# CFO_europroto_atmega328_mcp4822.net
KiCad netlist of a schematic drawn in EAGLE
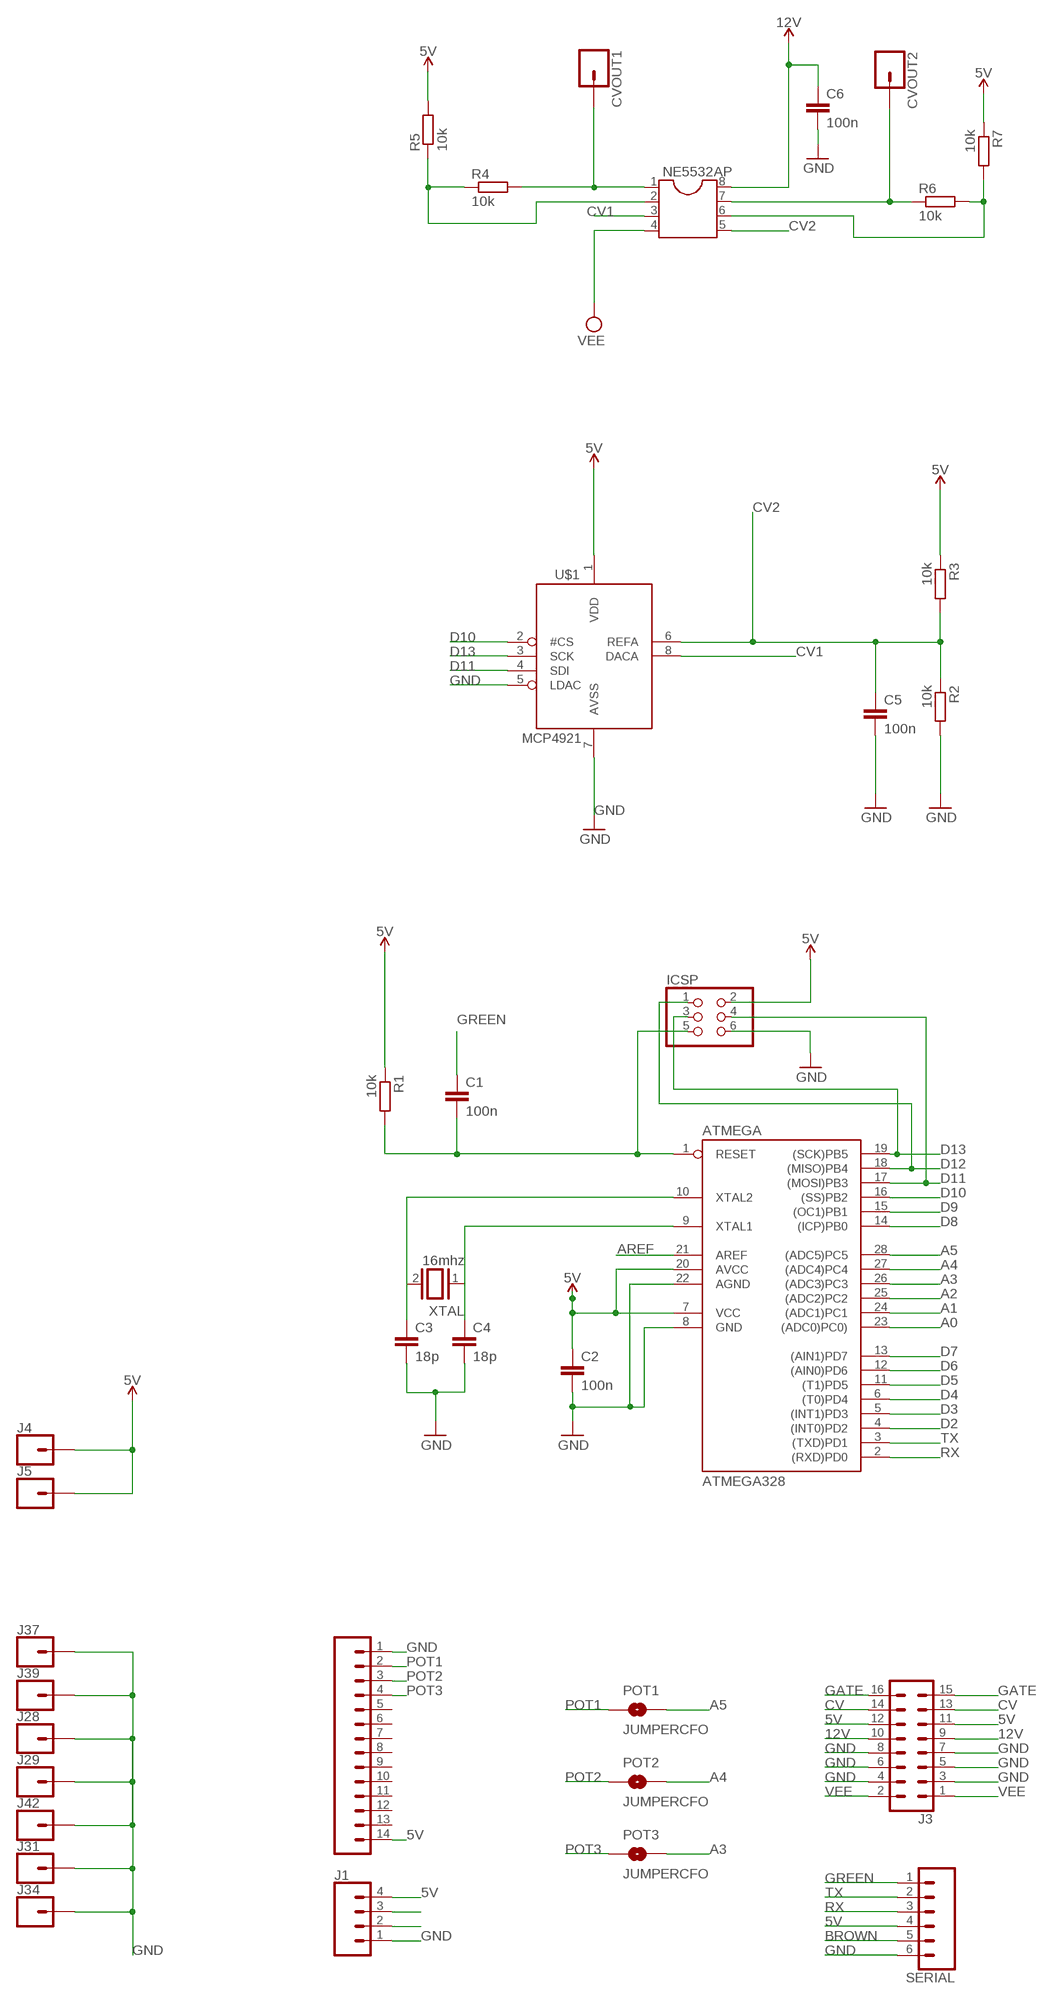
[diagram p0: schematic, sheet 1]

(export (version "E")
  (design (tool "Eeschema 10.0.6"))
  (components
    (comp (ref "ATMEGA")
      (value "ATMEGA328")
      (footprint "eagle-import:DIL28-3")
      (libsource (lib "eagle-import") (part "AT90S4433P"))
    )
    (comp (ref "C1")
      (value "100n")
      (footprint "eagle-import:C050-025X075")
      (libsource (lib "eagle-import") (part "C-EU050-025X075"))
    )
    (comp (ref "C2")
      (value "100n")
      (footprint "eagle-import:C050-025X075")
      (libsource (lib "eagle-import") (part "C-EU050-025X075"))
    )
    (comp (ref "C3")
      (value "18p")
      (footprint "eagle-import:C050-025X075")
      (libsource (lib "eagle-import") (part "C-EU050-025X075"))
    )
    (comp (ref "C4")
      (value "18p")
      (footprint "eagle-import:C050-025X075")
      (libsource (lib "eagle-import") (part "C-EU050-025X075"))
    )
    (comp (ref "C5")
      (value "100n")
      (footprint "eagle-import:C050-025X075")
      (libsource (lib "eagle-import") (part "C-EU050-025X075"))
    )
    (comp (ref "C6")
      (value "100n")
      (footprint "eagle-import:C050-025X075")
      (libsource (lib "eagle-import") (part "C-EU050-025X075"))
    )
    (comp (ref "CVOUT1")
      (value "CONN_01")
      (footprint "eagle-import:1X01")
      (libsource (lib "eagle-import") (part "CONN_01"))
    )
    (comp (ref "CVOUT2")
      (value "CONN_01")
      (footprint "eagle-import:1X01")
      (libsource (lib "eagle-import") (part "CONN_01"))
    )
    (comp (ref "ICSP")
      (value "PINHD-2X3")
      (footprint "eagle-import:2X03")
      (libsource (lib "eagle-import") (part "PINHD-2X3"))
    )
    (comp (ref "J1")
      (value "CONN_04")
      (footprint "eagle-import:1X04")
      (fields (field (name "SPICEPREFIX") "E"))
      (libsource (lib "eagle-import") (part "CONN_04"))
    )
    (comp (ref "J2")
      (value "CONN_14SQUARE")
      (footprint "eagle-import:1X14")
      (fields (field (name "SPICEPREFIX") "X"))
      (libsource (lib "eagle-import") (part "CONN_14SQUARE"))
    )
    (comp (ref "J3")
      (value "CONN_08X2_SHROUD")
      (footprint "eagle-import:2X8-SHROUDED_LOCK")
      (libsource (lib "eagle-import") (part "CONN_08X2_SHROUD"))
    )
    (comp (ref "J4")
      (value "CONN_01")
      (footprint "eagle-import:1X01")
      (libsource (lib "eagle-import") (part "CONN_01"))
    )
    (comp (ref "J5")
      (value "CONN_01")
      (footprint "eagle-import:1X01")
      (libsource (lib "eagle-import") (part "CONN_01"))
    )
    (comp (ref "J28")
      (value "CONN_01")
      (footprint "eagle-import:1X01")
      (libsource (lib "eagle-import") (part "CONN_01"))
    )
    (comp (ref "J29")
      (value "CONN_01")
      (footprint "eagle-import:1X01")
      (libsource (lib "eagle-import") (part "CONN_01"))
    )
    (comp (ref "J31")
      (value "CONN_01")
      (footprint "eagle-import:1X01")
      (libsource (lib "eagle-import") (part "CONN_01"))
    )
    (comp (ref "J34")
      (value "CONN_01")
      (footprint "eagle-import:1X01")
      (libsource (lib "eagle-import") (part "CONN_01"))
    )
    (comp (ref "J37")
      (value "CONN_01")
      (footprint "eagle-import:1X01")
      (libsource (lib "eagle-import") (part "CONN_01"))
    )
    (comp (ref "J39")
      (value "CONN_01")
      (footprint "eagle-import:1X01")
      (libsource (lib "eagle-import") (part "CONN_01"))
    )
    (comp (ref "J42")
      (value "CONN_01")
      (footprint "eagle-import:1X01")
      (libsource (lib "eagle-import") (part "CONN_01"))
    )
    (comp (ref "NE5532AP")
      (value "DIL8")
      (footprint "eagle-import:DIL08")
      (libsource (lib "eagle-import") (part "DIL8"))
    )
    (comp (ref "POT1")
      (value "JUMPERCFO")
      (footprint "eagle-import:SMT-JUMPER_2_NO_NO-SILK_ROUND")
      (libsource (lib "eagle-import") (part "JUMPERCFO"))
    )
    (comp (ref "POT2")
      (value "JUMPERCFO")
      (footprint "eagle-import:SMT-JUMPER_2_NO_NO-SILK_ROUND")
      (libsource (lib "eagle-import") (part "JUMPERCFO"))
    )
    (comp (ref "POT3")
      (value "JUMPERCFO")
      (footprint "eagle-import:SMT-JUMPER_2_NO_NO-SILK_ROUND")
      (libsource (lib "eagle-import") (part "JUMPERCFO"))
    )
    (comp (ref "R1")
      (value "10k")
      (footprint "eagle-import:0207_10")
      (libsource (lib "eagle-import") (part "R-EU_0207/10"))
    )
    (comp (ref "R2")
      (value "10k")
      (footprint "eagle-import:0207_10")
      (libsource (lib "eagle-import") (part "R-EU_0207/10"))
    )
    (comp (ref "R3")
      (value "10k")
      (footprint "eagle-import:0207_10")
      (libsource (lib "eagle-import") (part "R-EU_0207/10"))
    )
    (comp (ref "R4")
      (value "10k")
      (footprint "eagle-import:0207_10")
      (libsource (lib "eagle-import") (part "R-EU_0207/10"))
    )
    (comp (ref "R5")
      (value "10k")
      (footprint "eagle-import:0207_10")
      (libsource (lib "eagle-import") (part "R-EU_0207/10"))
    )
    (comp (ref "R6")
      (value "10k")
      (footprint "eagle-import:0207_10")
      (libsource (lib "eagle-import") (part "R-EU_0207/10"))
    )
    (comp (ref "R7")
      (value "10k")
      (footprint "eagle-import:0207_10")
      (libsource (lib "eagle-import") (part "R-EU_0207/10"))
    )
    (comp (ref "SERIAL")
      (value "CONN_06SILK_FEMALE_PTH")
      (footprint "eagle-import:1X06")
      (libsource (lib "eagle-import") (part "CONN_06SILK_FEMALE_PTH"))
    )
    (comp (ref "U$1")
      (value "MCP4921")
      (footprint "eagle-import:DIL08")
      (libsource (lib "eagle-import") (part "MCP4921"))
    )
    (comp (ref "XTAL")
      (value "16mhz")
      (footprint "eagle-import:QS")
      (libsource (lib "eagle-import") (part "XTAL/S"))
    )
  )
  (nets
    (net (code "1") (name "/A0") (class "Default")
      (node (ref "ATMEGA") (pin "23") (pinfunction "(ADC0)PC0)_23") (pintype "bidirectional"))
    )
    (net (code "2") (name "/A1") (class "Default")
      (node (ref "ATMEGA") (pin "24") (pinfunction "(ADC1)PC1_24") (pintype "bidirectional"))
    )
    (net (code "3") (name "/A2") (class "Default")
      (node (ref "ATMEGA") (pin "25") (pinfunction "(ADC2)PC2_25") (pintype "bidirectional"))
    )
    (net (code "4") (name "/A3") (class "Default")
      (node (ref "ATMEGA") (pin "26") (pinfunction "(ADC3)PC3_26") (pintype "bidirectional"))
      (node (ref "POT3") (pin "2") (pinfunction "2_2") (pintype "passive"))
    )
    (net (code "5") (name "/A4") (class "Default")
      (node (ref "ATMEGA") (pin "27") (pinfunction "(ADC4)PC4_27") (pintype "bidirectional"))
      (node (ref "POT2") (pin "2") (pinfunction "2_2") (pintype "passive"))
    )
    (net (code "6") (name "/A5") (class "Default")
      (node (ref "ATMEGA") (pin "28") (pinfunction "(ADC5)PC5_28") (pintype "bidirectional"))
      (node (ref "POT1") (pin "2") (pinfunction "2_2") (pintype "passive"))
    )
    (net (code "7") (name "/AREF") (class "Default")
      (node (ref "ATMEGA") (pin "21") (pinfunction "AREF_21") (pintype "passive"))
    )
    (net (code "8") (name "/BROWN") (class "Default")
      (node (ref "SERIAL") (pin "5") (pinfunction "5_5") (pintype "passive"))
    )
    (net (code "9") (name "/CV") (class "Default")
      (node (ref "J3") (pin "13") (pinfunction "13_13") (pintype "passive"))
      (node (ref "J3") (pin "14") (pinfunction "14_14") (pintype "passive"))
    )
    (net (code "10") (name "/CV1") (class "Default")
      (node (ref "NE5532AP") (pin "3") (pinfunction "3_3") (pintype "passive"))
      (node (ref "U$1") (pin "8") (pinfunction "DACA_8") (pintype "output"))
    )
    (net (code "11") (name "/CV2") (class "Default")
      (node (ref "C5") (pin "1") (pinfunction "1_1") (pintype "passive"))
      (node (ref "NE5532AP") (pin "5") (pinfunction "5_5") (pintype "passive"))
      (node (ref "R2") (pin "1") (pinfunction "1_1") (pintype "passive"))
      (node (ref "R3") (pin "2") (pinfunction "2_2") (pintype "passive"))
      (node (ref "U$1") (pin "6") (pinfunction "REFA_6") (pintype "input"))
    )
    (net (code "12") (name "/D2") (class "Default")
      (node (ref "ATMEGA") (pin "4") (pinfunction "(INT0)PD2_4") (pintype "bidirectional"))
    )
    (net (code "13") (name "/D3") (class "Default")
      (node (ref "ATMEGA") (pin "5") (pinfunction "(INT1)PD3_5") (pintype "bidirectional"))
    )
    (net (code "14") (name "/D4") (class "Default")
      (node (ref "ATMEGA") (pin "6") (pinfunction "(T0)PD4_6") (pintype "bidirectional"))
    )
    (net (code "15") (name "/D5") (class "Default")
      (node (ref "ATMEGA") (pin "11") (pinfunction "(T1)PD5_11") (pintype "bidirectional"))
    )
    (net (code "16") (name "/D6") (class "Default")
      (node (ref "ATMEGA") (pin "12") (pinfunction "(AIN0)PD6_12") (pintype "bidirectional"))
    )
    (net (code "17") (name "/D7") (class "Default")
      (node (ref "ATMEGA") (pin "13") (pinfunction "(AIN1)PD7_13") (pintype "bidirectional"))
    )
    (net (code "18") (name "/D8") (class "Default")
      (node (ref "ATMEGA") (pin "14") (pinfunction "(ICP)PB0_14") (pintype "bidirectional"))
    )
    (net (code "19") (name "/D9") (class "Default")
      (node (ref "ATMEGA") (pin "15") (pinfunction "(OC1)PB1_15") (pintype "bidirectional"))
    )
    (net (code "20") (name "/D10") (class "Default")
      (node (ref "ATMEGA") (pin "16") (pinfunction "(SS)PB2_16") (pintype "bidirectional"))
      (node (ref "U$1") (pin "2") (pinfunction "#CS_2") (pintype "input"))
    )
    (net (code "21") (name "/D11") (class "Default")
      (node (ref "ATMEGA") (pin "17") (pinfunction "(MOSI)PB3_17") (pintype "bidirectional"))
      (node (ref "ICSP") (pin "4") (pinfunction "4_4") (pintype "passive"))
      (node (ref "U$1") (pin "4") (pinfunction "SDI_4") (pintype "input"))
    )
    (net (code "22") (name "/D12") (class "Default")
      (node (ref "ATMEGA") (pin "18") (pinfunction "(MISO)PB4_18") (pintype "bidirectional"))
      (node (ref "ICSP") (pin "1") (pinfunction "1_1") (pintype "passive"))
    )
    (net (code "23") (name "/D13") (class "Default")
      (node (ref "ATMEGA") (pin "19") (pinfunction "(SCK)PB5_19") (pintype "bidirectional"))
      (node (ref "ICSP") (pin "3") (pinfunction "3_3") (pintype "passive"))
      (node (ref "U$1") (pin "3") (pinfunction "SCK_3") (pintype "input"))
    )
    (net (code "24") (name "/GATE") (class "Default")
      (node (ref "J3") (pin "15") (pinfunction "15_15") (pintype "passive"))
      (node (ref "J3") (pin "16") (pinfunction "16_16") (pintype "passive"))
    )
    (net (code "25") (name "/GREEN") (class "Default")
      (node (ref "C1") (pin "1") (pinfunction "1_1") (pintype "passive"))
      (node (ref "SERIAL") (pin "1") (pinfunction "1_1") (pintype "passive"))
    )
    (net (code "26") (name "/POT1") (class "Default")
      (node (ref "J2") (pin "2") (pinfunction "2_2") (pintype "passive"))
      (node (ref "POT1") (pin "1") (pinfunction "1_1") (pintype "passive"))
    )
    (net (code "27") (name "/POT2") (class "Default")
      (node (ref "J2") (pin "3") (pinfunction "3_3") (pintype "passive"))
      (node (ref "POT2") (pin "1") (pinfunction "1_1") (pintype "passive"))
    )
    (net (code "28") (name "/POT3") (class "Default")
      (node (ref "J2") (pin "4") (pinfunction "4_4") (pintype "passive"))
      (node (ref "POT3") (pin "1") (pinfunction "1_1") (pintype "passive"))
    )
    (net (code "29") (name "/RX") (class "Default")
      (node (ref "ATMEGA") (pin "2") (pinfunction "(RXD)PD0_2") (pintype "bidirectional"))
      (node (ref "SERIAL") (pin "3") (pinfunction "3_3") (pintype "passive"))
    )
    (net (code "30") (name "/TX") (class "Default")
      (node (ref "ATMEGA") (pin "3") (pinfunction "(TXD)PD1_3") (pintype "bidirectional"))
      (node (ref "SERIAL") (pin "2") (pinfunction "2_2") (pintype "passive"))
    )
    (net (code "31") (name "5V") (class "Default")
      (node (ref "ATMEGA") (pin "20") (pinfunction "AVCC_20") (pintype "power_in"))
      (node (ref "ATMEGA") (pin "7") (pinfunction "VCC_7") (pintype "power_in"))
      (node (ref "C2") (pin "1") (pinfunction "1_1") (pintype "passive"))
      (node (ref "ICSP") (pin "2") (pinfunction "2_2") (pintype "passive"))
      (node (ref "J1") (pin "4") (pinfunction "4_4") (pintype "passive"))
      (node (ref "J2") (pin "14") (pinfunction "14_14") (pintype "passive"))
      (node (ref "J3") (pin "11") (pinfunction "11_11") (pintype "passive"))
      (node (ref "J3") (pin "12") (pinfunction "12_12") (pintype "passive"))
      (node (ref "J4") (pin "1") (pinfunction "1_1") (pintype "passive"))
      (node (ref "J5") (pin "1") (pinfunction "1_1") (pintype "passive"))
      (node (ref "R1") (pin "1") (pinfunction "1_1") (pintype "passive"))
      (node (ref "R3") (pin "1") (pinfunction "1_1") (pintype "passive"))
      (node (ref "R5") (pin "2") (pinfunction "2_2") (pintype "passive"))
      (node (ref "R7") (pin "1") (pinfunction "1_1") (pintype "passive"))
      (node (ref "SERIAL") (pin "4") (pinfunction "4_4") (pintype "passive"))
      (node (ref "U$1") (pin "1") (pinfunction "VDD_1") (pintype "power_in"))
    )
    (net (code "32") (name "12V") (class "Default")
      (node (ref "C6") (pin "1") (pinfunction "1_1") (pintype "passive"))
      (node (ref "J3") (pin "10") (pinfunction "10_10") (pintype "passive"))
      (node (ref "J3") (pin "9") (pinfunction "9_9") (pintype "passive"))
      (node (ref "NE5532AP") (pin "8") (pinfunction "8_8") (pintype "passive"))
    )
    (net (code "33") (name "GND") (class "Default")
      (node (ref "ATMEGA") (pin "22") (pinfunction "AGND_22") (pintype "power_in"))
      (node (ref "ATMEGA") (pin "8") (pinfunction "GND_8") (pintype "power_in"))
      (node (ref "C2") (pin "2") (pinfunction "2_2") (pintype "passive"))
      (node (ref "C3") (pin "2") (pinfunction "2_2") (pintype "passive"))
      (node (ref "C4") (pin "2") (pinfunction "2_2") (pintype "passive"))
      (node (ref "C5") (pin "2") (pinfunction "2_2") (pintype "passive"))
      (node (ref "C6") (pin "2") (pinfunction "2_2") (pintype "passive"))
      (node (ref "ICSP") (pin "6") (pinfunction "6_6") (pintype "passive"))
      (node (ref "J1") (pin "1") (pinfunction "1_1") (pintype "passive"))
      (node (ref "J2") (pin "1") (pinfunction "1_1") (pintype "passive"))
      (node (ref "J28") (pin "1") (pinfunction "1_1") (pintype "passive"))
      (node (ref "J29") (pin "1") (pinfunction "1_1") (pintype "passive"))
      (node (ref "J3") (pin "3") (pinfunction "3_3") (pintype "passive"))
      (node (ref "J3") (pin "4") (pinfunction "4_4") (pintype "passive"))
      (node (ref "J3") (pin "5") (pinfunction "5_5") (pintype "passive"))
      (node (ref "J3") (pin "6") (pinfunction "6_6") (pintype "passive"))
      (node (ref "J3") (pin "7") (pinfunction "7_7") (pintype "passive"))
      (node (ref "J3") (pin "8") (pinfunction "8_8") (pintype "passive"))
      (node (ref "J31") (pin "1") (pinfunction "1_1") (pintype "passive"))
      (node (ref "J34") (pin "1") (pinfunction "1_1") (pintype "passive"))
      (node (ref "J37") (pin "1") (pinfunction "1_1") (pintype "passive"))
      (node (ref "J39") (pin "1") (pinfunction "1_1") (pintype "passive"))
      (node (ref "J42") (pin "1") (pinfunction "1_1") (pintype "passive"))
      (node (ref "R2") (pin "2") (pinfunction "2_2") (pintype "passive"))
      (node (ref "SERIAL") (pin "6") (pinfunction "6_6") (pintype "passive"))
      (node (ref "U$1") (pin "5") (pinfunction "LDAC_5") (pintype "input"))
      (node (ref "U$1") (pin "7") (pinfunction "AVSS_7") (pintype "power_in"))
    )
    (net (code "34") (name "Net-(ATMEGA-RESET)") (class "Default")
      (node (ref "ATMEGA") (pin "1") (pinfunction "RESET_1") (pintype "input"))
      (node (ref "C1") (pin "2") (pinfunction "2_2") (pintype "passive"))
      (node (ref "ICSP") (pin "5") (pinfunction "5_5") (pintype "passive"))
      (node (ref "R1") (pin "2") (pinfunction "2_2") (pintype "passive"))
    )
    (net (code "35") (name "Net-(ATMEGA-XTAL1)") (class "Default")
      (node (ref "ATMEGA") (pin "9") (pinfunction "XTAL1_9") (pintype "bidirectional"))
      (node (ref "C4") (pin "1") (pinfunction "1_1") (pintype "passive"))
      (node (ref "XTAL") (pin "1") (pinfunction "1_1") (pintype "passive"))
    )
    (net (code "36") (name "Net-(ATMEGA-XTAL2)") (class "Default")
      (node (ref "ATMEGA") (pin "10") (pinfunction "XTAL2_10") (pintype "bidirectional"))
      (node (ref "C3") (pin "1") (pinfunction "1_1") (pintype "passive"))
      (node (ref "XTAL") (pin "2") (pinfunction "2_2") (pintype "passive"))
    )
    (net (code "37") (name "Net-(CVOUT1-Pad1)") (class "Default")
      (node (ref "CVOUT1") (pin "1") (pinfunction "1_1") (pintype "passive"))
      (node (ref "NE5532AP") (pin "1") (pinfunction "1_1") (pintype "passive"))
      (node (ref "R4") (pin "2") (pinfunction "2_2") (pintype "passive"))
    )
    (net (code "38") (name "Net-(CVOUT2-Pad1)") (class "Default")
      (node (ref "CVOUT2") (pin "1") (pinfunction "1_1") (pintype "passive"))
      (node (ref "NE5532AP") (pin "7") (pinfunction "7_7") (pintype "passive"))
      (node (ref "R6") (pin "1") (pinfunction "1_1") (pintype "passive"))
    )
    (net (code "39") (name "Net-(NE5532AP-Pad2)") (class "Default")
      (node (ref "NE5532AP") (pin "2") (pinfunction "2_2") (pintype "passive"))
      (node (ref "R4") (pin "1") (pinfunction "1_1") (pintype "passive"))
      (node (ref "R5") (pin "1") (pinfunction "1_1") (pintype "passive"))
    )
    (net (code "40") (name "Net-(NE5532AP-Pad6)") (class "Default")
      (node (ref "NE5532AP") (pin "6") (pinfunction "6_6") (pintype "passive"))
      (node (ref "R6") (pin "2") (pinfunction "2_2") (pintype "passive"))
      (node (ref "R7") (pin "2") (pinfunction "2_2") (pintype "passive"))
    )
    (net (code "41") (name "VEE") (class "Default")
      (node (ref "J3") (pin "1") (pinfunction "1_1") (pintype "passive"))
      (node (ref "J3") (pin "2") (pinfunction "2_2") (pintype "passive"))
      (node (ref "NE5532AP") (pin "4") (pinfunction "4_4") (pintype "passive"))
    )
    (net (code "42") (name "unconnected-(J1-Pad2)") (class "Default")
      (node (ref "J1") (pin "2") (pinfunction "2_2") (pintype "passive"))
    )
    (net (code "43") (name "unconnected-(J1-Pad3)") (class "Default")
      (node (ref "J1") (pin "3") (pinfunction "3_3") (pintype "passive"))
    )
    (net (code "44") (name "unconnected-(J2-Pad5)") (class "Default")
      (node (ref "J2") (pin "5") (pinfunction "5_5") (pintype "passive"))
    )
    (net (code "45") (name "unconnected-(J2-Pad6)") (class "Default")
      (node (ref "J2") (pin "6") (pinfunction "6_6") (pintype "passive"))
    )
    (net (code "46") (name "unconnected-(J2-Pad7)") (class "Default")
      (node (ref "J2") (pin "7") (pinfunction "7_7") (pintype "passive"))
    )
    (net (code "47") (name "unconnected-(J2-Pad8)") (class "Default")
      (node (ref "J2") (pin "8") (pinfunction "8_8") (pintype "passive"))
    )
    (net (code "48") (name "unconnected-(J2-Pad9)") (class "Default")
      (node (ref "J2") (pin "9") (pinfunction "9_9") (pintype "passive"))
    )
    (net (code "49") (name "unconnected-(J2-Pad10)") (class "Default")
      (node (ref "J2") (pin "10") (pinfunction "10_10") (pintype "passive"))
    )
    (net (code "50") (name "unconnected-(J2-Pad11)") (class "Default")
      (node (ref "J2") (pin "11") (pinfunction "11_11") (pintype "passive"))
    )
    (net (code "51") (name "unconnected-(J2-Pad12)") (class "Default")
      (node (ref "J2") (pin "12") (pinfunction "12_12") (pintype "passive"))
    )
    (net (code "52") (name "unconnected-(J2-Pad13)") (class "Default")
      (node (ref "J2") (pin "13") (pinfunction "13_13") (pintype "passive"))
    )
  )
)
